# 5G_2.net
KiCad netlist of a schematic drawn in Altium Designer
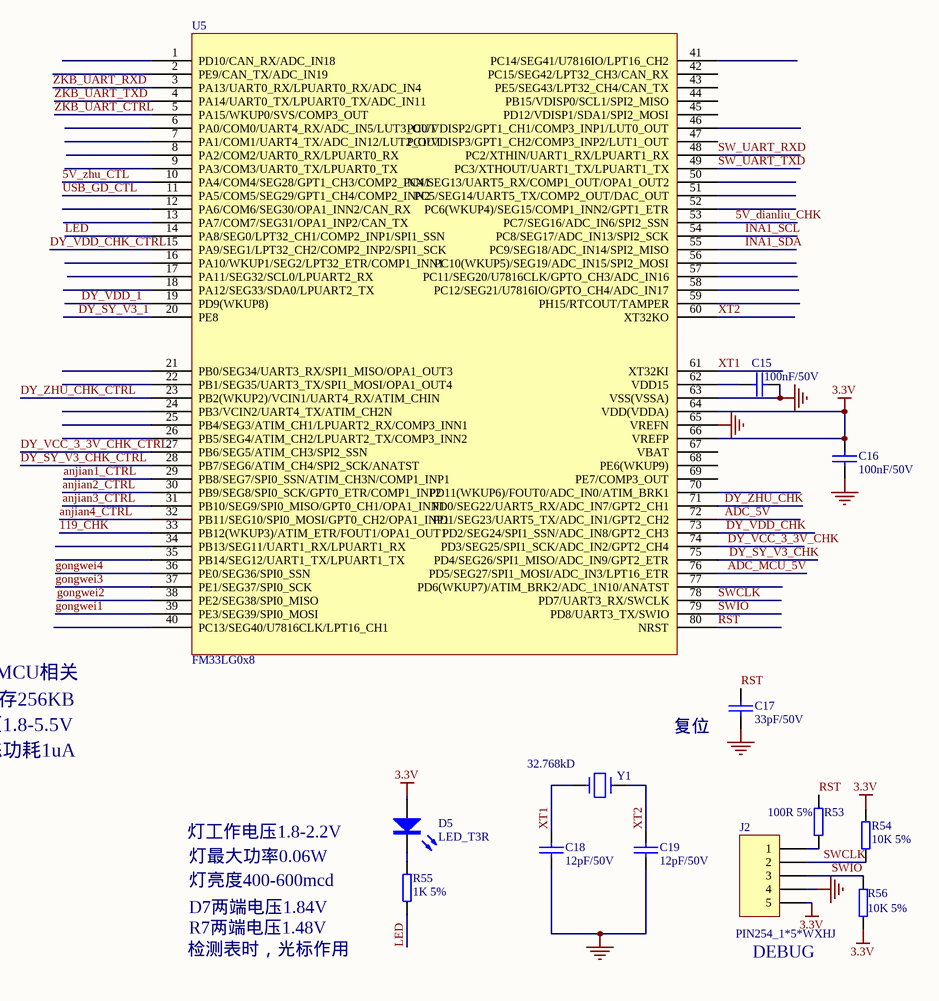
[diagram p0: 5G智慧网关工装2.SchDoc]

(export (version "E")
  (design (tool "Eeschema 10.0.6"))
  (components
    (comp (ref "C15")
      (value "100nF/50V")
      (footprint "CAP0603")
      (description "104pF,50 V,±10%,0603,国巨,CC0603KRX7R9BB104")
      (fields (field (name "PART NUMBER") "101020103-0021"))
      (libsource (lib "Database_Libs2") (part "CC03K7R9_100N"))
    )
    (comp (ref "C16")
      (value "100nF/50V")
      (footprint "CAP0603")
      (description "104pF,50 V,±10%,0603,国巨,CC0603KRX7R9BB104")
      (fields (field (name "PART NUMBER") "101020103-0021"))
      (libsource (lib "Database_Libs2") (part "CC03K7R9_100N"))
    )
    (comp (ref "C17")
      (value "33pF/50V")
      (footprint "CAP0603")
      (description "33pF,50 V,±10%,0603,国巨,CC0603KRNPO9BN33")
      (fields (field (name "PART NUMBER") "101020103-0027"))
      (libsource (lib "Database_Libs2") (part "CC03KPO9_33P"))
    )
    (comp (ref "C18")
      (value "12pF/50V")
      (footprint "CAP0603")
      (description "12P,50 V,±5%,0603,国巨,CC0603JRNPO9BN12")
      (fields (field (name "PART NUMBER") "101020103-0005"))
      (libsource (lib "Database_Libs2") (part "CC03JPO9_12P"))
    )
    (comp (ref "C19")
      (value "12pF/50V")
      (footprint "CAP0603")
      (description "12P,50 V,±5%,0603,国巨,CC0603JRNPO9BN12")
      (fields (field (name "PART NUMBER") "101020103-0005"))
      (libsource (lib "Database_Libs2") (part "CC03JPO9_12P"))
    )
    (comp (ref "D5")
      (value "LED_T3R")
      (footprint "LED2_300")
      (description "圆形插件,3mm 圆形,插件,红光,湖北匡通电子有限公司,3BB4HC")
      (fields (field (name "PART NUMBER") "101040102-0001"))
      (libsource (lib "Database_Libs2") (part "01-LED_T3R"))
    )
    (comp (ref "J2")
      (value "PIN254_1*5*WXHJ")
      (footprint "PIN254_1*5*1100S")
      (description "1*5 ，Φ1.0 ，2.54mm，直脚,无需焊接器件")
      (fields (field (name "PART NUMBER") "AD_WXHJ_PinHeader_02"))
      (libsource (lib "Database_Libs2") (part "PIN254_1*5*1100S"))
    )
    (comp (ref "R53")
      (value "100R 5%")
      (footprint "RES0603")
      (description "100R,±5%,1/10W,0603,国巨,RC0603JR-07100RL")
      (fields (field (name "PART NUMBER") "101010103-0022"))
      (libsource (lib "Database_Libs2") (part "RC03J_100R"))
    )
    (comp (ref "R54")
      (value "10K 5%")
      (footprint "RES0603")
      (description "国巨,±5%,0603,,155 ℃,-55 ℃,RC0603JR-0710KL,无铅,200 ppm/℃,1/10W,,10K")
      (fields (field (name "PART NUMBER") "101010103-0003"))
      (libsource (lib "Database_Libs2") (part "RC03J_10K"))
    )
    (comp (ref "R55")
      (value "1K 5%")
      (footprint "RES0603")
      (description "1K,±5%,1/10W,0603,国巨,RC0603JR-071KL")
      (fields (field (name "PART NUMBER") "101010103-0008"))
      (libsource (lib "Database_Libs2") (part "RC03J_1K"))
    )
    (comp (ref "R56")
      (value "10K 5%")
      (footprint "RES0603")
      (description "国巨,±5%,0603,,155 ℃,-55 ℃,RC0603JR-0710KL,无铅,200 ppm/℃,1/10W,,10K")
      (fields (field (name "PART NUMBER") "101010103-0003"))
      (libsource (lib "Database_Libs2") (part "RC03J_10K"))
    )
    (comp (ref "U5") (value "FM33LG0x8") (footprint "LQFP80") (libsource (lib "FM_MCU") (part "FM33LG0x8")))
    (comp (ref "Y1")
      (value "32.768kD")
      (footprint "SMD-3215_2P")
      (fields (field (name "PART NUMBER") "1010601-0020"))
      (libsource (lib "Database_Libs2") (part "04_XTALSG12MD_32.768kD"))
    )
  )
  (nets
    (net (code "1") (name "/5V_dianliu_CHK") (class "Default")
      (node (ref "U5") (pin "53") (pinfunction "PC7/SEG16/ADC_IN6/SPI2_SSN_53") (pintype "passive"))
    )
    (net (code "2") (name "/5V_zhu_CTL") (class "Default")
      (node (ref "U5") (pin "10") (pinfunction "PA4/COM4/SEG28/GPT1_CH3/COMP2_INN1_10") (pintype "passive"))
    )
    (net (code "3") (name "/119_CHK") (class "Default")
      (node (ref "U5") (pin "33") (pinfunction "PB12(WKUP3)/ATIM_ETR/FOUT1/OPA1_OUT1_33") (pintype "passive"))
    )
    (net (code "4") (name "/ADC_5V") (class "Default")
      (node (ref "U5") (pin "72") (pinfunction "PD1/SEG23/UART5_TX/ADC_IN1/GPT2_CH2_72") (pintype "passive"))
    )
    (net (code "5") (name "/ADC_MCU_5V") (class "Default")
      (node (ref "U5") (pin "76") (pinfunction "PD5/SEG27/SPI1_MOSI/ADC_IN3/LPT16_ETR_76") (pintype "passive"))
    )
    (net (code "6") (name "/DY_SY_V3_1") (class "Default")
      (node (ref "U5") (pin "20") (pinfunction "PE8_20") (pintype "passive"))
    )
    (net (code "7") (name "/DY_SY_V3_CHK") (class "Default")
      (node (ref "U5") (pin "75") (pinfunction "PD4/SEG26/SPI1_MISO/ADC_IN9/GPT2_ETR_75") (pintype "passive"))
    )
    (net (code "8") (name "/DY_SY_V3_CHK_CTRL") (class "Default")
      (node (ref "U5") (pin "28") (pinfunction "PB7/SEG6/ATIM_CH4/SPI2_SCK/ANATST_28") (pintype "passive"))
    )
    (net (code "9") (name "/DY_VCC_3_3V_CHK") (class "Default")
      (node (ref "U5") (pin "74") (pinfunction "PD3/SEG25/SPI1_SCK/ADC_IN2/GPT2_CH4_74") (pintype "passive"))
    )
    (net (code "10") (name "/DY_VCC_3_3V_CHK_CTRL") (class "Default")
      (node (ref "U5") (pin "27") (pinfunction "PB6/SEG5/ATIM_CH3/SPI2_SSN_27") (pintype "passive"))
    )
    (net (code "11") (name "/DY_VDD_1") (class "Default")
      (node (ref "U5") (pin "19") (pinfunction "PD9(WKUP8)_19") (pintype "passive"))
    )
    (net (code "12") (name "/DY_VDD_CHK") (class "Default")
      (node (ref "U5") (pin "73") (pinfunction "PD2/SEG24/SPI1_SSN/ADC_IN8/GPT2_CH3_73") (pintype "passive"))
    )
    (net (code "13") (name "/DY_VDD_CHK_CTRL") (class "Default")
      (node (ref "U5") (pin "15") (pinfunction "PA9/SEG1/LPT32_CH2/COMP2_INP2/SPI1_SCK_15") (pintype "passive"))
    )
    (net (code "14") (name "/DY_ZHU_CHK") (class "Default")
      (node (ref "U5") (pin "71") (pinfunction "PD0/SEG22/UART5_RX/ADC_IN7/GPT2_CH1_71") (pintype "passive"))
    )
    (net (code "15") (name "/DY_ZHU_CHK_CTRL") (class "Default")
      (node (ref "U5") (pin "23") (pinfunction "PB2(WKUP2)/VCIN1/UART4_RX/ATIM_CHIN_23") (pintype "passive"))
    )
    (net (code "16") (name "/INA1_SCL") (class "Default")
      (node (ref "U5") (pin "54") (pinfunction "PC8/SEG17/ADC_IN13/SPI2_SCK_54") (pintype "passive"))
    )
    (net (code "17") (name "/INA1_SDA") (class "Default")
      (node (ref "U5") (pin "55") (pinfunction "PC9/SEG18/ADC_IN14/SPI2_MISO_55") (pintype "passive"))
    )
    (net (code "18") (name "/LED") (class "Default")
      (node (ref "R55") (pin "1") (pinfunction "1_1") (pintype "passive"))
      (node (ref "U5") (pin "14") (pinfunction "PA8/SEG0/LPT32_CH1/COMP2_INP1/SPI1_SSN_14") (pintype "passive"))
    )
    (net (code "19") (name "/RST") (class "Default")
      (node (ref "C17") (pin "1") (pinfunction "1_1") (pintype "passive"))
      (node (ref "R53") (pin "1") (pinfunction "1_1") (pintype "passive"))
      (node (ref "U5") (pin "80") (pinfunction "NRST_80") (pintype "passive"))
    )
    (net (code "20") (name "/SWCLK") (class "Default")
      (node (ref "J2") (pin "2") (pinfunction "2_2") (pintype "passive"))
      (node (ref "R54") (pin "2") (pinfunction "2_2") (pintype "passive"))
      (node (ref "U5") (pin "78") (pinfunction "PD7/UART3_RX/SWCLK_78") (pintype "passive"))
    )
    (net (code "21") (name "/SWIO") (class "Default")
      (node (ref "J2") (pin "3") (pinfunction "3_3") (pintype "passive"))
      (node (ref "R56") (pin "2") (pinfunction "2_2") (pintype "passive"))
      (node (ref "U5") (pin "79") (pinfunction "PD8/UART3_TX/SWIO_79") (pintype "passive"))
    )
    (net (code "22") (name "/SW_UART_RXD") (class "Default")
      (node (ref "U5") (pin "48") (pinfunction "PC2/XTHIN/UART1_RX/LPUART1_RX_48") (pintype "passive"))
    )
    (net (code "23") (name "/SW_UART_TXD") (class "Default")
      (node (ref "U5") (pin "49") (pinfunction "PC3/XTHOUT/UART1_TX/LPUART1_TX_49") (pintype "passive"))
    )
    (net (code "24") (name "/USB_GD_CTL") (class "Default")
      (node (ref "U5") (pin "11") (pinfunction "PA5/COM5/SEG29/GPT1_CH4/COMP2_INN2_11") (pintype "passive"))
    )
    (net (code "25") (name "/XT1") (class "Default")
      (node (ref "C18") (pin "1") (pinfunction "1_1") (pintype "passive"))
      (node (ref "U5") (pin "61") (pinfunction "XT32KI_61") (pintype "passive"))
      (node (ref "Y1") (pin "1") (pinfunction "1_1") (pintype "passive"))
    )
    (net (code "26") (name "/XT2") (class "Default")
      (node (ref "C19") (pin "2") (pinfunction "2_2") (pintype "passive"))
      (node (ref "U5") (pin "60") (pinfunction "XT32KO_60") (pintype "passive"))
      (node (ref "Y1") (pin "2") (pinfunction "2_2") (pintype "passive"))
    )
    (net (code "27") (name "/ZKB_UART_CTRL") (class "Default")
      (node (ref "U5") (pin "5") (pinfunction "PA15/WKUP0/SVS/COMP3_OUT_5") (pintype "passive"))
    )
    (net (code "28") (name "/ZKB_UART_RXD") (class "Default")
      (node (ref "U5") (pin "3") (pinfunction "PA13/UART0_RX/LPUART0_RX/ADC_IN4_3") (pintype "passive"))
    )
    (net (code "29") (name "/ZKB_UART_TXD") (class "Default")
      (node (ref "U5") (pin "4") (pinfunction "PA14/UART0_TX/LPUART0_TX/ADC_IN11_4") (pintype "passive"))
    )
    (net (code "30") (name "/anjian1_CTRL") (class "Default")
      (node (ref "U5") (pin "29") (pinfunction "PB8/SEG7/SPI0_SSN/ATIM_CH3N/COMP1_INP1_29") (pintype "passive"))
    )
    (net (code "31") (name "/anjian2_CTRL") (class "Default")
      (node (ref "U5") (pin "30") (pinfunction "PB9/SEG8/SPI0_SCK/GPT0_ETR/COMP1_INP2_30") (pintype "passive"))
    )
    (net (code "32") (name "/anjian3_CTRL") (class "Default")
      (node (ref "U5") (pin "31") (pinfunction "PB10/SEG9/SPI0_MISO/GPT0_CH1/OPA1_INN1_31") (pintype "passive"))
    )
    (net (code "33") (name "/anjian4_CTRL") (class "Default")
      (node (ref "U5") (pin "32") (pinfunction "PB11/SEG10/SPI0_MOSI/GPT0_CH2/OPA1_INP1_32") (pintype "passive"))
    )
    (net (code "34") (name "/gongwei1") (class "Default")
      (node (ref "U5") (pin "39") (pinfunction "PE3/SEG39/SPI0_MOSI_39") (pintype "passive"))
    )
    (net (code "35") (name "/gongwei2") (class "Default")
      (node (ref "U5") (pin "38") (pinfunction "PE2/SEG38/SPI0_MISO_38") (pintype "passive"))
    )
    (net (code "36") (name "/gongwei3") (class "Default")
      (node (ref "U5") (pin "37") (pinfunction "PE1/SEG37/SPI0_SCK_37") (pintype "passive"))
    )
    (net (code "37") (name "/gongwei4") (class "Default")
      (node (ref "U5") (pin "36") (pinfunction "PE0/SEG36/SPI0_SSN_36") (pintype "passive"))
    )
    (net (code "38") (name "3.3V") (class "Default")
      (node (ref "C16") (pin "2") (pinfunction "2_2") (pintype "passive"))
      (node (ref "D5") (pin "1") (pinfunction "1_1") (pintype "passive"))
      (node (ref "J2") (pin "5") (pinfunction "5_5") (pintype "passive"))
      (node (ref "R54") (pin "1") (pinfunction "1_1") (pintype "passive"))
      (node (ref "R56") (pin "1") (pinfunction "1_1") (pintype "passive"))
      (node (ref "U5") (pin "64") (pinfunction "VDD(VDDA)_64") (pintype "passive"))
      (node (ref "U5") (pin "66") (pinfunction "VREFP_66") (pintype "passive"))
    )
    (net (code "39") (name "GND") (class "Default")
      (node (ref "C15") (pin "2") (pinfunction "2_2") (pintype "passive"))
      (node (ref "C16") (pin "1") (pinfunction "1_1") (pintype "passive"))
      (node (ref "C17") (pin "2") (pinfunction "2_2") (pintype "passive"))
      (node (ref "C18") (pin "2") (pinfunction "2_2") (pintype "passive"))
      (node (ref "C19") (pin "1") (pinfunction "1_1") (pintype "passive"))
      (node (ref "J2") (pin "4") (pinfunction "4_4") (pintype "passive"))
      (node (ref "U5") (pin "63") (pinfunction "VSS(VSSA)_63") (pintype "passive"))
      (node (ref "U5") (pin "65") (pinfunction "VREFN_65") (pintype "passive"))
    )
    (net (code "40") (name "Net-(D5-Pad2)") (class "Default")
      (node (ref "D5") (pin "2") (pinfunction "2_2") (pintype "passive"))
      (node (ref "R55") (pin "2") (pinfunction "2_2") (pintype "passive"))
    )
    (net (code "41") (name "Net-(J2-Pad1)") (class "Default")
      (node (ref "J2") (pin "1") (pinfunction "1_1") (pintype "passive"))
      (node (ref "R53") (pin "2") (pinfunction "2_2") (pintype "passive"))
    )
    (net (code "42") (name "Net-(U5-VDD15)") (class "Default")
      (node (ref "C15") (pin "1") (pinfunction "1_1") (pintype "passive"))
      (node (ref "U5") (pin "62") (pinfunction "VDD15_62") (pintype "passive"))
    )
    (net (code "43") (name "unconnected-(U5-PA0{slash}COM0{slash}UART4_RX{slash}ADC_IN5{slash}LUT3_OUT-Pad6)") (class "Default")
      (node (ref "U5") (pin "6") (pinfunction "PA0/COM0/UART4_RX/ADC_IN5/LUT3_OUT_6") (pintype "passive"))
    )
    (net (code "44") (name "unconnected-(U5-PA1{slash}COM1{slash}UART4_TX{slash}ADC_IN12{slash}LUT2_OUT-Pad7)") (class "Default")
      (node (ref "U5") (pin "7") (pinfunction "PA1/COM1/UART4_TX/ADC_IN12/LUT2_OUT_7") (pintype "passive"))
    )
    (net (code "45") (name "unconnected-(U5-PA2{slash}COM2{slash}UART0_RX{slash}LPUART0_RX-Pad8)") (class "Default")
      (node (ref "U5") (pin "8") (pinfunction "PA2/COM2/UART0_RX/LPUART0_RX_8") (pintype "passive"))
    )
    (net (code "46") (name "unconnected-(U5-PA3{slash}COM3{slash}UART0_TX{slash}LPUART0_TX-Pad9)") (class "Default")
      (node (ref "U5") (pin "9") (pinfunction "PA3/COM3/UART0_TX/LPUART0_TX_9") (pintype "passive"))
    )
    (net (code "47") (name "unconnected-(U5-PA6{slash}COM6{slash}SEG30{slash}OPA1_INN2{slash}CAN_RX-Pad12)") (class "Default")
      (node (ref "U5") (pin "12") (pinfunction "PA6/COM6/SEG30/OPA1_INN2/CAN_RX_12") (pintype "passive"))
    )
    (net (code "48") (name "unconnected-(U5-PA7{slash}COM7{slash}SEG31{slash}OPA1_INP2{slash}CAN_TX-Pad13)") (class "Default")
      (node (ref "U5") (pin "13") (pinfunction "PA7/COM7/SEG31/OPA1_INP2/CAN_TX_13") (pintype "passive"))
    )
    (net (code "49") (name "unconnected-(U5-PA10{slash}WKUP1{slash}SEG2{slash}LPT32_ETR{slash}COMP1_INN1-Pad16)") (class "Default")
      (node (ref "U5") (pin "16") (pinfunction "PA10/WKUP1/SEG2/LPT32_ETR/COMP1_INN1_16") (pintype "passive"))
    )
    (net (code "50") (name "unconnected-(U5-PA11{slash}SEG32{slash}SCL0{slash}LPUART2_RX-Pad17)") (class "Default")
      (node (ref "U5") (pin "17") (pinfunction "PA11/SEG32/SCL0/LPUART2_RX_17") (pintype "passive"))
    )
    (net (code "51") (name "unconnected-(U5-PA12{slash}SEG33{slash}SDA0{slash}LPUART2_TX-Pad18)") (class "Default")
      (node (ref "U5") (pin "18") (pinfunction "PA12/SEG33/SDA0/LPUART2_TX_18") (pintype "passive"))
    )
    (net (code "52") (name "unconnected-(U5-PB0{slash}SEG34{slash}UART3_RX{slash}SPI1_MISO{slash}OPA1_OUT3-Pad21)") (class "Default")
      (node (ref "U5") (pin "21") (pinfunction "PB0/SEG34/UART3_RX/SPI1_MISO/OPA1_OUT3_21") (pintype "passive"))
    )
    (net (code "53") (name "unconnected-(U5-PB1{slash}SEG35{slash}UART3_TX{slash}SPI1_MOSI{slash}OPA1_OUT4-Pad22)") (class "Default")
      (node (ref "U5") (pin "22") (pinfunction "PB1/SEG35/UART3_TX/SPI1_MOSI/OPA1_OUT4_22") (pintype "passive"))
    )
    (net (code "54") (name "unconnected-(U5-PB3{slash}VCIN2{slash}UART4_TX{slash}ATIM_CH2N-Pad24)") (class "Default")
      (node (ref "U5") (pin "24") (pinfunction "PB3/VCIN2/UART4_TX/ATIM_CH2N_24") (pintype "passive"))
    )
    (net (code "55") (name "unconnected-(U5-PB4{slash}SEG3{slash}ATIM_CH1{slash}LPUART2_RX{slash}COMP3_INN1-Pad25)") (class "Default")
      (node (ref "U5") (pin "25") (pinfunction "PB4/SEG3/ATIM_CH1/LPUART2_RX/COMP3_INN1_25") (pintype "passive"))
    )
    (net (code "56") (name "unconnected-(U5-PB5{slash}SEG4{slash}ATIM_CH2{slash}LPUART2_TX{slash}COMP3_INN2-Pad26)") (class "Default")
      (node (ref "U5") (pin "26") (pinfunction "PB5/SEG4/ATIM_CH2/LPUART2_TX/COMP3_INN2_26") (pintype "passive"))
    )
    (net (code "57") (name "unconnected-(U5-PB13{slash}SEG11{slash}UART1_RX{slash}LPUART1_RX-Pad34)") (class "Default")
      (node (ref "U5") (pin "34") (pinfunction "PB13/SEG11/UART1_RX/LPUART1_RX_34") (pintype "passive"))
    )
    (net (code "58") (name "unconnected-(U5-PB14{slash}SEG12{slash}UART1_TX{slash}LPUART1_TX-Pad35)") (class "Default")
      (node (ref "U5") (pin "35") (pinfunction "PB14/SEG12/UART1_TX/LPUART1_TX_35") (pintype "passive"))
    )
    (net (code "59") (name "unconnected-(U5-PB15{slash}VDISP0{slash}SCL1{slash}SPI2_MISO-Pad44)") (class "Default")
      (node (ref "U5") (pin "44") (pinfunction "PB15/VDISP0/SCL1/SPI2_MISO_44") (pintype "passive"))
    )
    (net (code "60") (name "unconnected-(U5-PC0{slash}VDISP2{slash}GPT1_CH1{slash}COMP3_INP1{slash}LUT0_OUT-Pad46)") (class "Default")
      (node (ref "U5") (pin "46") (pinfunction "PC0/VDISP2/GPT1_CH1/COMP3_INP1/LUT0_OUT_46") (pintype "passive"))
    )
    (net (code "61") (name "unconnected-(U5-PC1{slash}VDISP3{slash}GPT1_CH2{slash}COMP3_INP2{slash}LUT1_OUT-Pad47)") (class "Default")
      (node (ref "U5") (pin "47") (pinfunction "PC1/VDISP3/GPT1_CH2/COMP3_INP2/LUT1_OUT_47") (pintype "passive"))
    )
    (net (code "62") (name "unconnected-(U5-PC4{slash}SEG13{slash}UART5_RX{slash}COMP1_OUT{slash}OPA1_OUT2-Pad50)") (class "Default")
      (node (ref "U5") (pin "50") (pinfunction "PC4/SEG13/UART5_RX/COMP1_OUT/OPA1_OUT2_50") (pintype "passive"))
    )
    (net (code "63") (name "unconnected-(U5-PC5{slash}SEG14{slash}UART5_TX{slash}COMP2_OUT{slash}DAC_OUT-Pad51)") (class "Default")
      (node (ref "U5") (pin "51") (pinfunction "PC5/SEG14/UART5_TX/COMP2_OUT/DAC_OUT_51") (pintype "passive"))
    )
    (net (code "64") (name "unconnected-(U5-PC6(WKUP4){slash}SEG15{slash}COMP1_INN2{slash}GPT1_ETR-Pad52)") (class "Default")
      (node (ref "U5") (pin "52") (pinfunction "PC6(WKUP4)/SEG15/COMP1_INN2/GPT1_ETR_52") (pintype "passive"))
    )
    (net (code "65") (name "unconnected-(U5-PC10(WKUP5){slash}SEG19{slash}ADC_IN15{slash}SPI2_MOSI-Pad56)") (class "Default")
      (node (ref "U5") (pin "56") (pinfunction "PC10(WKUP5)/SEG19/ADC_IN15/SPI2_MOSI_56") (pintype "passive"))
    )
    (net (code "66") (name "unconnected-(U5-PC11{slash}SEG20{slash}U7816CLK{slash}GPTO_CH3{slash}ADC_IN16-Pad57)") (class "Default")
      (node (ref "U5") (pin "57") (pinfunction "PC11/SEG20/U7816CLK/GPTO_CH3/ADC_IN16_57") (pintype "passive"))
    )
    (net (code "67") (name "unconnected-(U5-PC12{slash}SEG21{slash}U7816IO{slash}GPTO_CH4{slash}ADC_IN17-Pad58)") (class "Default")
      (node (ref "U5") (pin "58") (pinfunction "PC12/SEG21/U7816IO/GPTO_CH4/ADC_IN17_58") (pintype "passive"))
    )
    (net (code "68") (name "unconnected-(U5-PC13{slash}SEG40{slash}U7816CLK{slash}LPT16_CH1-Pad40)") (class "Default")
      (node (ref "U5") (pin "40") (pinfunction "PC13/SEG40/U7816CLK/LPT16_CH1_40") (pintype "passive"))
    )
    (net (code "69") (name "unconnected-(U5-PC14{slash}SEG41{slash}U7816IO{slash}LPT16_CH2-Pad41)") (class "Default")
      (node (ref "U5") (pin "41") (pinfunction "PC14/SEG41/U7816IO/LPT16_CH2_41") (pintype "passive"))
    )
    (net (code "70") (name "unconnected-(U5-PC15{slash}SEG42{slash}LPT32_CH3{slash}CAN_RX-Pad42)") (class "Default")
      (node (ref "U5") (pin "42") (pinfunction "PC15/SEG42/LPT32_CH3/CAN_RX_42") (pintype "passive"))
    )
    (net (code "71") (name "unconnected-(U5-PD6(WKUP7){slash}ATIM_BRK2{slash}ADC_1N10{slash}ANATST-Pad77)") (class "Default")
      (node (ref "U5") (pin "77") (pinfunction "PD6(WKUP7)/ATIM_BRK2/ADC_1N10/ANATST_77") (pintype "passive"))
    )
    (net (code "72") (name "unconnected-(U5-PD10{slash}CAN_RX{slash}ADC_IN18-Pad1)") (class "Default")
      (node (ref "U5") (pin "1") (pinfunction "PD10/CAN_RX/ADC_IN18_1") (pintype "passive"))
    )
    (net (code "73") (name "unconnected-(U5-PD11(WKUP6){slash}FOUT0{slash}ADC_IN0{slash}ATIM_BRK1-Pad70)") (class "Default")
      (node (ref "U5") (pin "70") (pinfunction "PD11(WKUP6)/FOUT0/ADC_IN0/ATIM_BRK1_70") (pintype "passive"))
    )
    (net (code "74") (name "unconnected-(U5-PD12{slash}VDISP1{slash}SDA1{slash}SPI2_MOSI-Pad45)") (class "Default")
      (node (ref "U5") (pin "45") (pinfunction "PD12/VDISP1/SDA1/SPI2_MOSI_45") (pintype "passive"))
    )
    (net (code "75") (name "unconnected-(U5-PE5{slash}SEG43{slash}LPT32_CH4{slash}CAN_TX-Pad43)") (class "Default")
      (node (ref "U5") (pin "43") (pinfunction "PE5/SEG43/LPT32_CH4/CAN_TX_43") (pintype "passive"))
    )
    (net (code "76") (name "unconnected-(U5-PE6(WKUP9)-Pad68)") (class "Default")
      (node (ref "U5") (pin "68") (pinfunction "PE6(WKUP9)_68") (pintype "passive"))
    )
    (net (code "77") (name "unconnected-(U5-PE7{slash}COMP3_OUT-Pad69)") (class "Default")
      (node (ref "U5") (pin "69") (pinfunction "PE7/COMP3_OUT_69") (pintype "passive"))
    )
    (net (code "78") (name "unconnected-(U5-PE9{slash}CAN_TX{slash}ADC_IN19-Pad2)") (class "Default")
      (node (ref "U5") (pin "2") (pinfunction "PE9/CAN_TX/ADC_IN19_2") (pintype "passive"))
    )
    (net (code "79") (name "unconnected-(U5-PH15{slash}RTCOUT{slash}TAMPER-Pad59)") (class "Default")
      (node (ref "U5") (pin "59") (pinfunction "PH15/RTCOUT/TAMPER_59") (pintype "passive"))
    )
    (net (code "80") (name "unconnected-(U5-VBAT-Pad67)") (class "Default")
      (node (ref "U5") (pin "67") (pinfunction "VBAT_67") (pintype "passive"))
    )
  )
)
